# ProPrj_LED__2025-12-03-09-07-42.net
KiCad netlist of a schematic drawn in EasyEDA Pro
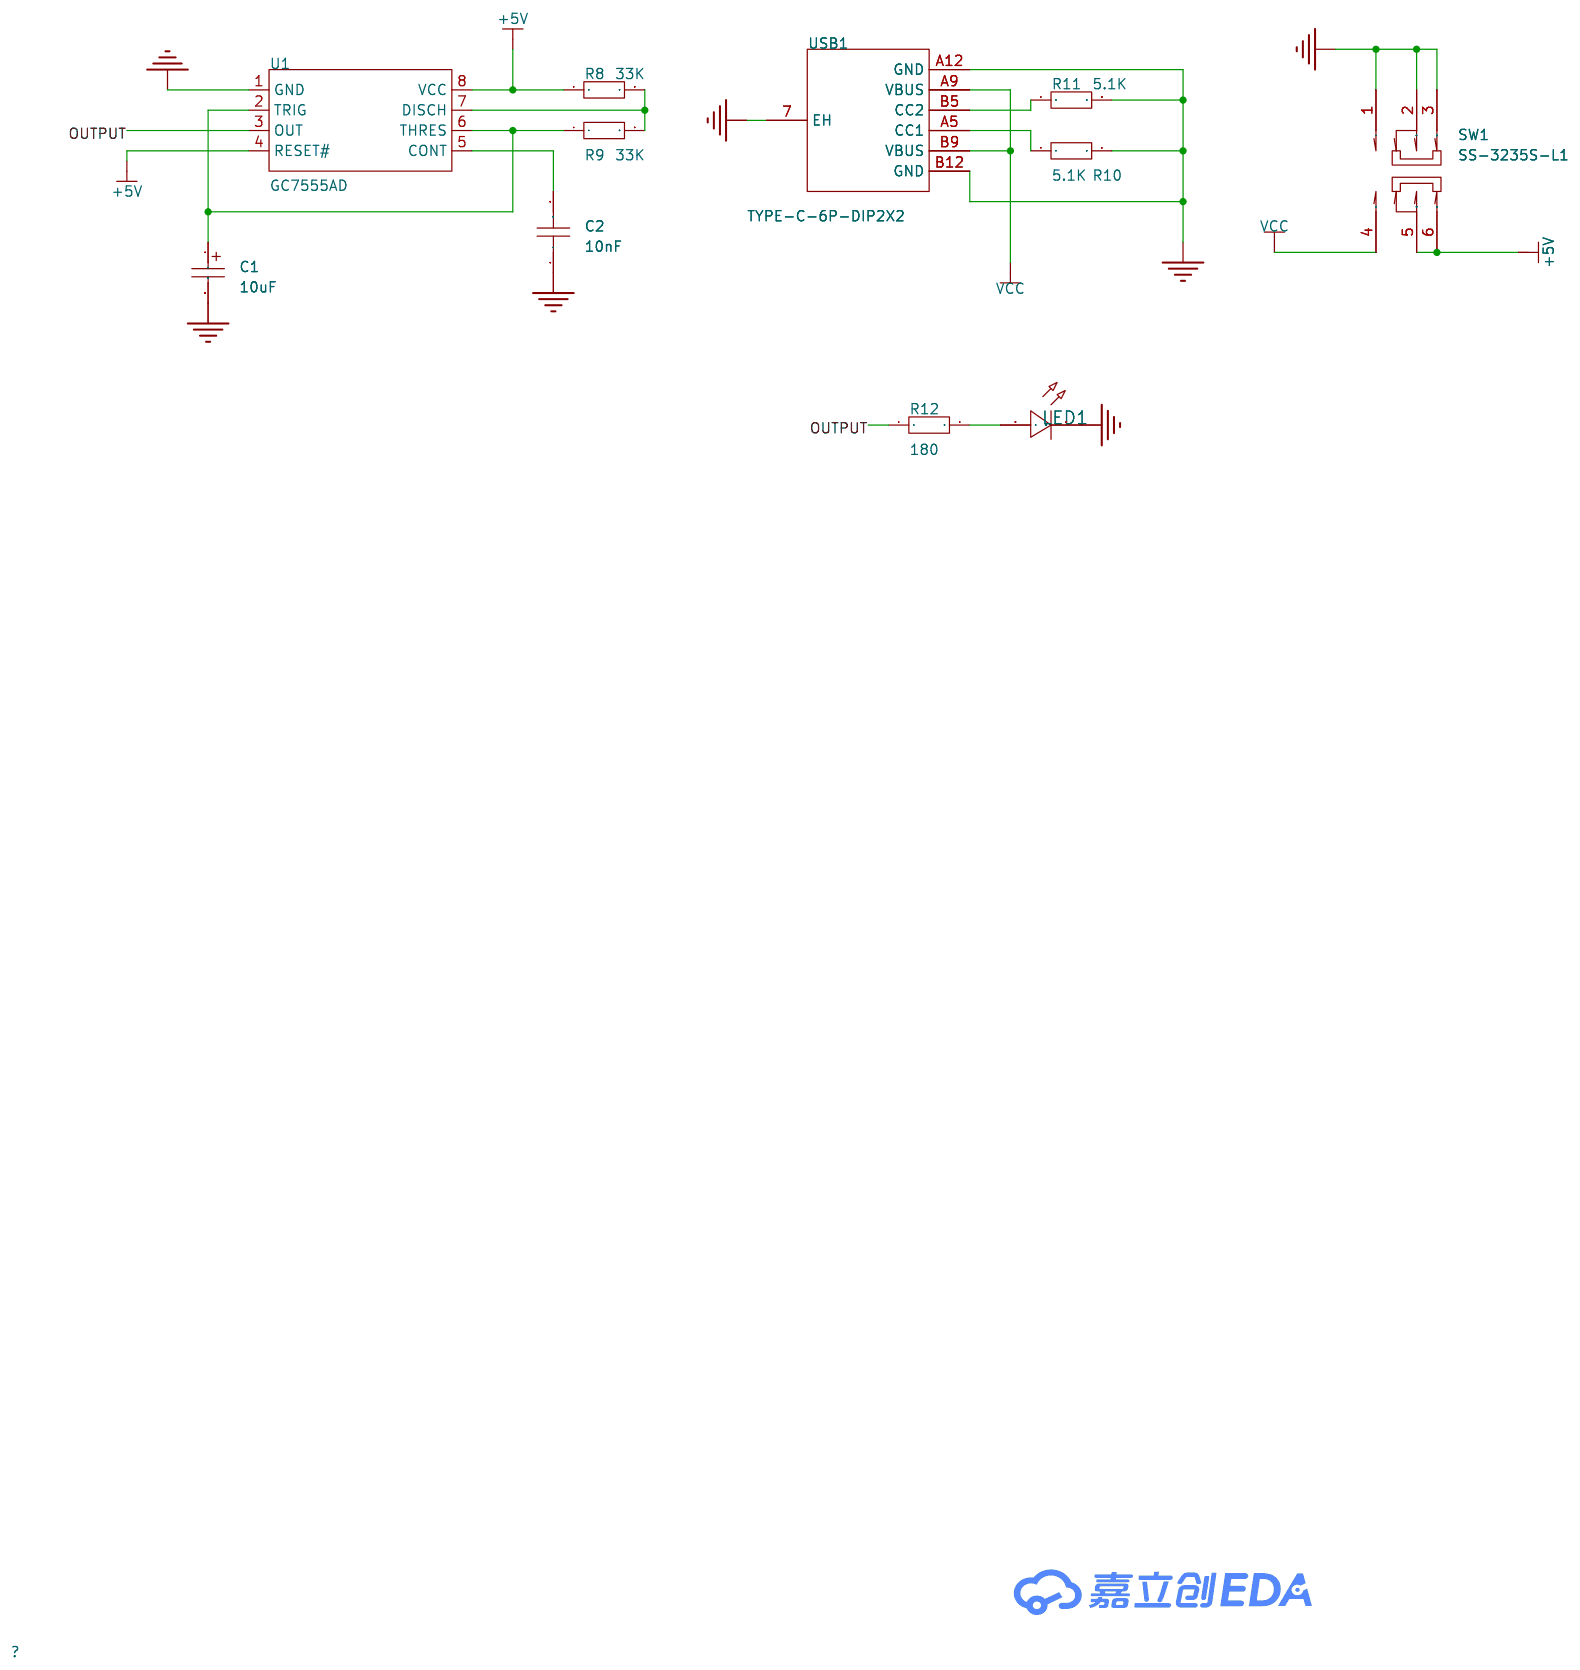
[diagram p0: schematic sheet]

(export (version "E")
  (design (tool "Eeschema 10.0.6"))
  (components
    (comp (ref "C1")
      (value "10uF")
      (footprint "easyedapro:C_Ele_SMD_3x5.4mm")
      (libsource (lib "easyedapro") (part "CAP"))
    )
    (comp (ref "C2")
      (value "10nF")
      (footprint "easyedapro:C0603")
      (libsource (lib "easyedapro") (part "Capacitance"))
    )
    (comp (ref "LED1")
      (value "~")
      (footprint "easyedapro:LED_0603")
      (libsource (lib "easyedapro") (part "LED_R"))
    )
    (comp (ref "R8") (value "33K") (footprint "easyedapro:R0805") (libsource (lib "easyedapro") (part "电阻")))
    (comp (ref "R9") (value "33K") (footprint "easyedapro:R0805") (libsource (lib "easyedapro") (part "电阻")))
    (comp (ref "R10")
      (value "5.1K")
      (footprint "easyedapro:R0805")
      (libsource (lib "easyedapro") (part "电阻"))
    )
    (comp (ref "R11")
      (value "5.1K")
      (footprint "easyedapro:R0805")
      (libsource (lib "easyedapro") (part "电阻"))
    )
    (comp (ref "R12") (value "180") (footprint "easyedapro:R0805") (libsource (lib "easyedapro") (part "电阻")))
    (comp (ref "SW1")
      (value "SS-3235S-L1")
      (footprint "easyedapro:SW-SMD_SS-3235S-LX")
      (description "电路结构:双刀双掷;安装方式:卧贴;开关颜色:黑色;额定电流:50mA;额定电压:12V;工作寿命:1万次;")
      (fields (field (name "Manufacturer") "XKB Connection(中国星坤)"))
      (libsource (lib "easyedapro") (part "SS-3235S-L1"))
    )
    (comp (ref "U1")
      (value "GC7555AD")
      (footprint "easyedapro:PDIP-8_L9.5-W6.4-P2.54-LS7.6-BL")
      (description "通用计时器：时基电路；计时；脉冲产生；满足用户（至少工业级）自主可控的需求。")
      (fields (field (name "Manufacturer") "Sungine(双竞集成)"))
      (libsource (lib "easyedapro") (part "GC7555AD"))
    )
    (comp (ref "USB1")
      (value "TYPE-C-6P-DIP2X2")
      (footprint "easyedapro:TYPE-C-SMD_TYPE-C-6P")
      (libsource (lib "easyedapro") (part "TYPE-C-6P-DIP2X2"))
    )
  )
  (nets
    (net (code "1") (name "+5V") (class "Default")
      (node (ref "R8") (pin "1") (pinfunction "1_1") (pintype "input"))
      (node (ref "SW1") (pin "5") (pinfunction "5_5") (pintype "unspecified"))
      (node (ref "SW1") (pin "6") (pinfunction "6_6") (pintype "unspecified"))
      (node (ref "U1") (pin "4") (pinfunction "RESET#_4") (pintype "unspecified"))
      (node (ref "U1") (pin "8") (pinfunction "VCC_8") (pintype "unspecified"))
    )
    (net (code "2") (name "/OUTPUT") (class "Default")
      (node (ref "R12") (pin "1") (pinfunction "1_1") (pintype "input"))
      (node (ref "U1") (pin "3") (pinfunction "OUT_3") (pintype "unspecified"))
    )
    (net (code "3") (name "GND") (class "Default")
      (node (ref "C1") (pin "2") (pinfunction "2_2") (pintype "input"))
      (node (ref "C2") (pin "1") (pinfunction "1_1") (pintype "input"))
      (node (ref "LED1") (pin "1") (pinfunction "C_1") (pintype "input"))
      (node (ref "R10") (pin "2") (pinfunction "2_2") (pintype "input"))
      (node (ref "R11") (pin "2") (pinfunction "2_2") (pintype "input"))
      (node (ref "SW1") (pin "1") (pinfunction "1_1") (pintype "unspecified"))
      (node (ref "SW1") (pin "2") (pinfunction "2_2") (pintype "unspecified"))
      (node (ref "SW1") (pin "3") (pinfunction "3_3") (pintype "unspecified"))
      (node (ref "U1") (pin "1") (pinfunction "GND_1") (pintype "unspecified"))
      (node (ref "USB1") (pin "7") (pinfunction "EH_7") (pintype "unspecified"))
      (node (ref "USB1") (pin "A12") (pinfunction "GND_A12") (pintype "unspecified"))
      (node (ref "USB1") (pin "B12") (pinfunction "GND_B12") (pintype "unspecified"))
    )
    (net (code "4") (name "Net-(LED1-A)") (class "Default")
      (node (ref "LED1") (pin "2") (pinfunction "A_2") (pintype "input"))
      (node (ref "R12") (pin "2") (pinfunction "2_2") (pintype "input"))
    )
    (net (code "5") (name "Net-(U1-CONT)") (class "Default")
      (node (ref "C2") (pin "2") (pinfunction "2_2") (pintype "input"))
      (node (ref "U1") (pin "5") (pinfunction "CONT_5") (pintype "unspecified"))
    )
    (net (code "6") (name "Net-(U1-DISCH)") (class "Default")
      (node (ref "R8") (pin "2") (pinfunction "2_2") (pintype "input"))
      (node (ref "R9") (pin "2") (pinfunction "2_2") (pintype "input"))
      (node (ref "U1") (pin "7") (pinfunction "DISCH_7") (pintype "unspecified"))
    )
    (net (code "7") (name "Net-(U1-THRES)") (class "Default")
      (node (ref "C1") (pin "1") (pinfunction "1_1") (pintype "input"))
      (node (ref "R9") (pin "1") (pinfunction "1_1") (pintype "input"))
      (node (ref "U1") (pin "2") (pinfunction "TRIG_2") (pintype "unspecified"))
      (node (ref "U1") (pin "6") (pinfunction "THRES_6") (pintype "unspecified"))
    )
    (net (code "8") (name "Net-(USB1-CC1)") (class "Default")
      (node (ref "R10") (pin "1") (pinfunction "1_1") (pintype "input"))
      (node (ref "USB1") (pin "A5") (pinfunction "CC1_A5") (pintype "unspecified"))
    )
    (net (code "9") (name "Net-(USB1-CC2)") (class "Default")
      (node (ref "R11") (pin "1") (pinfunction "1_1") (pintype "input"))
      (node (ref "USB1") (pin "B5") (pinfunction "CC2_B5") (pintype "unspecified"))
    )
    (net (code "10") (name "VCC") (class "Default")
      (node (ref "SW1") (pin "4") (pinfunction "4_4") (pintype "unspecified"))
      (node (ref "USB1") (pin "A9") (pinfunction "VBUS_A9") (pintype "unspecified"))
      (node (ref "USB1") (pin "B9") (pinfunction "VBUS_B9") (pintype "unspecified"))
    )
  )
)
